# TIDA-PowerNBIoT_Buck.net
KiCad netlist of a schematic drawn in Altium Designer
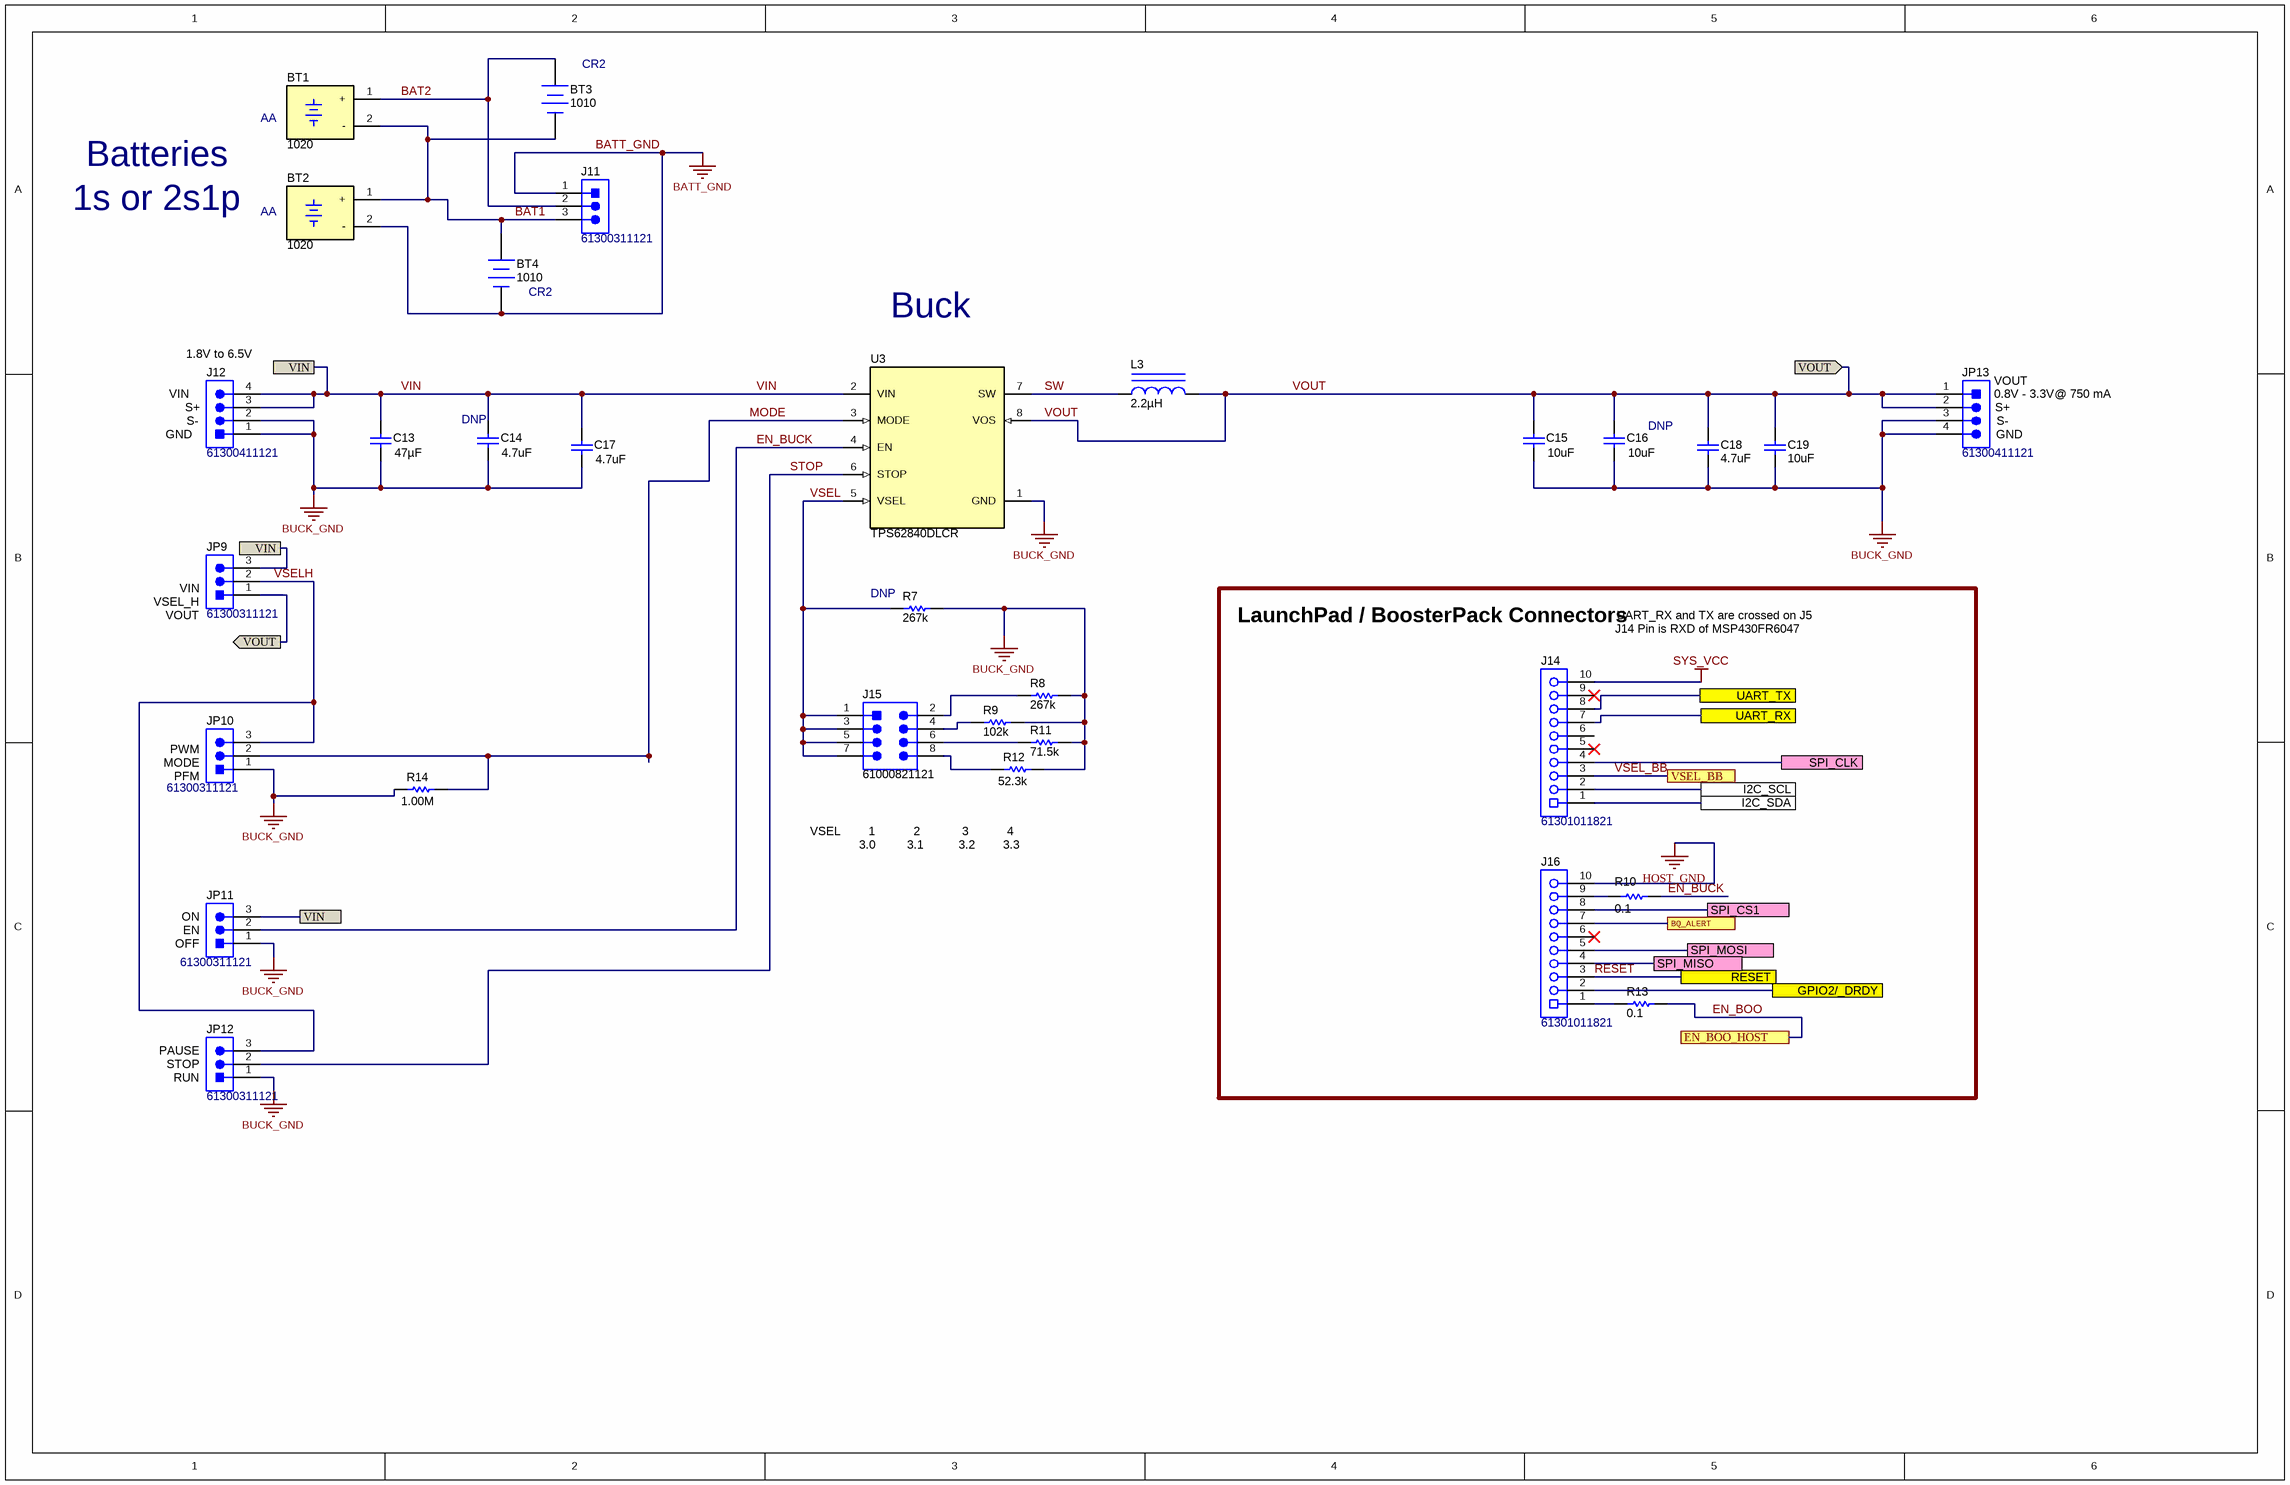
[diagram p0: TIDA-PowerNBIoT_Buck.SchDoc]

(export (version "E")
  (design (tool "Eeschema 10.0.6"))
  (components
    (comp (ref "BT1")
      (value "1020")
      (footprint "Keystone_1020")
      (description "HOLDER BATTERY AAA, SMT")
      (fields (field (name "MANUFACTURER") "Keystone") (field (name "PUBLISHER") "Texas Instruments"))
      (libsource (lib "Altium Vault - TI") (part "BatteryHolder_9V"))
    )
    (comp (ref "BT2")
      (value "1020")
      (footprint "Keystone_1020")
      (description "HOLDER BATTERY AAA, SMT")
      (fields (field (name "MANUFACTURER") "Keystone") (field (name "PUBLISHER") "Texas Instruments"))
      (libsource (lib "Altium Vault - TI") (part "BatteryHolder_9V"))
    )
    (comp (ref "BT3")
      (value "1010")
      (footprint "BAT_1010")
      (description "Battery Holder, Nylon, CR2, SMT")
      (fields (field (name "MANUFACTURER") "Keystone") (field (name "PUBLISHER") "Texas Instruments"))
      (libsource (lib "Altium Vault - TI") (part "Battery"))
    )
    (comp (ref "BT4")
      (value "1010")
      (footprint "BAT_1010")
      (description "Battery Holder, Nylon, CR2, SMT")
      (fields (field (name "MANUFACTURER") "Keystone") (field (name "PUBLISHER") "Texas Instruments"))
      (libsource (lib "Altium Vault - TI") (part "Battery"))
    )
    (comp (ref "C13")
      (value "GRM21BR61A476ME15L")
      (footprint "0805_HV")
      (description "CAP, CERM, 47 µF, 10 V,+/- 20%, X5R, 0805")
      (fields (field (name "MANUFACTURER") "MuRata") (field (name "VALUEDISPLAYED") "47µF"))
      (libsource (lib "Altium Vault - TI") (part "CMP-0078699-1"))
    )
    (comp (ref "C14")
      (value "GRM155R61A475MEAAD")
      (footprint "0402S")
      (description "CAP, CERM, 4.7 uF, 10 V, +/- 20%, X5R, 0402")
      (fields
        (field (name "MANUFACTURER") "MuRata")
        (field (name "VALUEDISPLAYED") "4.7uF")
        (field (name "PUBLISHER") "Texas Instruments")
      )
      (libsource (lib "Altium Vault - TI") (part "CMP-0006582-2"))
    )
    (comp (ref "C15")
      (value "GRM155R60G106ME44D")
      (footprint "0402_070")
      (description "CAP, CERM, 10 uF, 4 V, +/- 20%, X5R, 0402")
      (fields
        (field (name "MANUFACTURER") "MuRata")
        (field (name "VALUEDISPLAYED") "10uF")
        (field (name "PUBLISHER") "Texas Instruments")
      )
      (libsource (lib "Altium Vault - TI") (part "Capacitor"))
    )
    (comp (ref "C16")
      (value "GRM155R60G106ME44D")
      (footprint "0402_070")
      (description "CAP, CERM, 10 uF, 4 V, +/- 20%, X5R, 0402")
      (fields
        (field (name "MANUFACTURER") "MuRata")
        (field (name "VALUEDISPLAYED") "10uF")
        (field (name "PUBLISHER") "Texas Instruments")
      )
      (libsource (lib "Altium Vault - TI") (part "Capacitor"))
    )
    (comp (ref "C17")
      (value "GRM155R61A475MEAAD")
      (footprint "0402S")
      (description "CAP, CERM, 4.7 uF, 10 V, +/- 20%, X5R, 0402")
      (fields
        (field (name "MANUFACTURER") "MuRata")
        (field (name "VALUEDISPLAYED") "4.7uF")
        (field (name "PUBLISHER") "Texas Instruments")
      )
      (libsource (lib "Altium Vault - TI") (part "CMP-0006582-2"))
    )
    (comp (ref "C18")
      (value "GRM188R60J475ME19D")
      (footprint "0603S")
      (description "CAP, CERM, 4.7 uF, 6.3 V, +/- 20%, X5R, 0603")
      (fields
        (field (name "VALUEDISPLAYED") "4.7uF")
        (field (name "MANUFACTURER") "MuRata")
        (field (name "PUBLISHER") "Texas Instruments")
      )
      (libsource (lib "Altium Vault - TI") (part "CMP-0007312-5"))
    )
    (comp (ref "C19")
      (value "GRM21BR70J106KE76L")
      (footprint "0805_HV")
      (description "CAP, CERM, 10 uF, 6.3 V, +/- 10%, X7R, 0805")
      (fields
        (field (name "VALUEDISPLAYED") "10uF")
        (field (name "MANUFACTURER") "MuRata")
        (field (name "PUBLISHER") "Texas Instruments")
      )
      (libsource (lib "Altium Vault - TI") (part "Capacitor"))
    )
    (comp (ref "J11")
      (value "61300311121")
      (footprint "WURTH_61300311121")
      (description "Header, 2.54 mm, 3x1, Gold, TH")
      (fields (field (name "MANUFACTURER") "Wurth Elektronik"))
      (libsource (lib "") (part "Header_3x1_1"))
    )
    (comp (ref "J12")
      (value "61300411121")
      (footprint "WURTH_61300411121")
      (description "Header, 2.54 mm, 4x1, Gold, TH")
      (fields (field (name "MANUFACTURER") "Wurth Elektronik"))
      (libsource (lib "Altium Vault - TI") (part "Header_4x1"))
    )
    (comp (ref "J14")
      (value "61301011821")
      (footprint "Wurth_61301011821")
      (description "Receptacle, 2.54mm, 10x1, Gold, TH")
      (fields (field (name "MANUFACTURER") "Wurth Elektronik") (field (name "PUBLISHER") "Texas Instruments"))
      (libsource (lib "Altium Vault - TI") (part "Receptacle_10x1"))
    )
    (comp (ref "J15")
      (value "61000821121")
      (footprint "Wurth_61000821121")
      (description "Header, 2.54mm, 4x2, Gold, SMT")
      (fields (field (name "MANUFACTURER") "Wurth Elektronik"))
      (libsource (lib "Altium Vault - TI") (part "Header_4x2"))
    )
    (comp (ref "J16")
      (value "61301011821")
      (footprint "Wurth_61301011821")
      (description "Receptacle, 2.54mm, 10x1, Gold, TH")
      (fields (field (name "MANUFACTURER") "Wurth Elektronik") (field (name "PUBLISHER") "Texas Instruments"))
      (libsource (lib "Altium Vault - TI") (part "Receptacle_10x1"))
    )
    (comp (ref "JP9")
      (value "61300311121")
      (footprint "WURTH_61300311121")
      (description "Header, 2.54 mm, 3x1, Gold, TH")
      (fields (field (name "MANUFACTURER") "Wurth Elektronik"))
      (libsource (lib "Altium Vault - TI") (part "Header_3x1"))
    )
    (comp (ref "JP10")
      (value "61300311121")
      (footprint "WURTH_61300311121")
      (description "Header, 2.54 mm, 3x1, Gold, TH")
      (fields (field (name "MANUFACTURER") "Wurth Elektronik"))
      (libsource (lib "Altium Vault - TI") (part "Header_3x1"))
    )
    (comp (ref "JP11")
      (value "61300311121")
      (footprint "WURTH_61300311121")
      (description "Header, 2.54 mm, 3x1, Gold, TH")
      (fields (field (name "MANUFACTURER") "Wurth Elektronik"))
      (libsource (lib "Altium Vault - TI") (part "Header_3x1"))
    )
    (comp (ref "JP12")
      (value "61300311121")
      (footprint "WURTH_61300311121")
      (description "Header, 2.54 mm, 3x1, Gold, TH")
      (fields (field (name "MANUFACTURER") "Wurth Elektronik"))
      (libsource (lib "Altium Vault - TI") (part "Header_3x1"))
    )
    (comp (ref "JP13")
      (value "61300411121")
      (footprint "WURTH_61300411121")
      (description "Header, 2.54 mm, 4x1, Gold, TH")
      (fields (field (name "MANUFACTURER") "Wurth Elektronik"))
      (libsource (lib "") (part "Header_4x1_1"))
    )
    (comp (ref "L3")
      (value "DFE201612E-2R2M=P2")
      (footprint "DFE201612E")
      (description "Inductor, Shielded, Metal Composite, 2.2 µH, 1.8 A, 0.116 ohm, SMD")
      (fields (field (name "MANUFACTURER") "MuRata") (field (name "VALUEDISPLAYED") "2.2µH"))
      (libsource (lib "Altium Vault - TI") (part "Inductor_Iron"))
    )
    (comp (ref "R7")
      (value "ERJ-2RKF2673X")
      (footprint "0402")
      (description "RES, 267 k, 1%, 0.1 W, AEC-Q200 Grade 0, 0402")
      (fields
        (field (name "MANUFACTURER") "Panasonic")
        (field (name "VALUEDISPLAYED") "267k")
        (field (name "PUBLISHER") "Texas Instruments")
      )
      (libsource (lib "Altium Vault - TI") (part "Resistor"))
    )
    (comp (ref "R8")
      (value "ERJ-2RKF2673X")
      (footprint "0402")
      (description "RES, 267 k, 1%, 0.1 W, AEC-Q200 Grade 0, 0402")
      (fields
        (field (name "MANUFACTURER") "Panasonic")
        (field (name "VALUEDISPLAYED") "267k")
        (field (name "PUBLISHER") "Texas Instruments")
      )
      (libsource (lib "Altium Vault - TI") (part "Resistor"))
    )
    (comp (ref "R9")
      (value "CRCW0402102KFKED")
      (footprint "0402")
      (description "RES, 102 k, 1%, 0.063 W, 0402")
      (fields
        (field (name "MANUFACTURER") "Vishay-Dale")
        (field (name "VALUEDISPLAYED") "102k")
        (field (name "PUBLISHER") "Texas Instruments")
      )
      (libsource (lib "Altium Vault - TI") (part "Resistor"))
    )
    (comp (ref "R10")
      (value "ERJ-2BSFR10X")
      (footprint "0402")
      (description "RES, 0.1, 1%, 0.125 W, AEC-Q200 Grade 0, 0402")
      (fields (field (name "MANUFACTURER") "Panasonic") (field (name "VALUEDISPLAYED") "0.1"))
      (libsource (lib "Altium Vault - TI") (part "Resistor"))
    )
    (comp (ref "R11")
      (value "CRCW040271K5FKED")
      (footprint "0402")
      (description "RES, 71.5 k, 1%, 0.063 W, AEC-Q200 Grade 0, 0402")
      (fields (field (name "MANUFACTURER") "Vishay-Dale") (field (name "VALUEDISPLAYED") "71.5k"))
      (libsource (lib "Altium Vault - TI") (part "Resistor"))
    )
    (comp (ref "R12")
      (value "CRCW040252K3FKED")
      (footprint "0402")
      (description "RES, 52.3 k, 1%, 0.063 W, AEC-Q200 Grade 0, 0402")
      (fields (field (name "MANUFACTURER") "Vishay-Dale") (field (name "VALUEDISPLAYED") "52.3k"))
      (libsource (lib "Altium Vault - TI") (part "Resistor"))
    )
    (comp (ref "R13")
      (value "ERJ-2BSFR10X")
      (footprint "0402")
      (description "RES, 0.1, 1%, 0.125 W, AEC-Q200 Grade 0, 0402")
      (fields (field (name "MANUFACTURER") "Panasonic") (field (name "VALUEDISPLAYED") "0.1"))
      (libsource (lib "Altium Vault - TI") (part "Resistor"))
    )
    (comp (ref "R14")
      (value "CRCW04021M00FKED")
      (footprint "0402")
      (description "RES, 1.00 M, 1%, 0.063 W, AEC-Q200 Grade 0, 0402")
      (fields (field (name "MANUFACTURER") "Vishay-Dale") (field (name "VALUEDISPLAYED") "1.00M"))
      (libsource (lib "Altium Vault - TI") (part "Resistor"))
    )
    (comp (ref "U3")
      (value "TPS62840DLCR")
      (footprint "DLC0008B")
      (description "Ultra low IQ Step Down Converter, DLC0008A (VSON-HR-8)")
      (fields (field (name "MANUFACTURER") "Texas Instruments") (field (name "PARTNUMBER") "TPS62840DLCR"))
      (libsource (lib "Altium Vault - TI") (part "TPS6284xDLC"))
    )
  )
  (nets
    (net (code "1") (name "/BAT1") (class "Default")
      (node (ref "BT1") (pin "2") (pinfunction "-_2") (pintype "passive"))
      (node (ref "BT2") (pin "1") (pinfunction "+_1") (pintype "passive"))
      (node (ref "BT3") (pin "2") (pinfunction "-_2") (pintype "passive"))
      (node (ref "BT4") (pin "1") (pinfunction "+_1") (pintype "passive"))
      (node (ref "J11") (pin "3") (pinfunction "3_3") (pintype "passive"))
    )
    (net (code "2") (name "/BAT2") (class "Default")
      (node (ref "BT1") (pin "1") (pinfunction "+_1") (pintype "passive"))
      (node (ref "BT3") (pin "1") (pinfunction "+_1") (pintype "passive"))
      (node (ref "J11") (pin "2") (pinfunction "2_2") (pintype "passive"))
    )
    (net (code "3") (name "/BQ_ALERT") (class "Default")
      (node (ref "J16") (pin "7") (pinfunction "7_7") (pintype "passive"))
    )
    (net (code "4") (name "/EN_BOO") (class "Default")
      (node (ref "R13") (pin "2") (pinfunction "2_2") (pintype "passive"))
    )
    (net (code "5") (name "/EN_BUCK") (class "Default")
      (node (ref "JP11") (pin "2") (pinfunction "2_2") (pintype "passive"))
      (node (ref "R10") (pin "2") (pinfunction "2_2") (pintype "passive"))
      (node (ref "U3") (pin "4") (pinfunction "EN_4") (pintype "input"))
    )
    (net (code "6") (name "/GPIO2{slash}_DRDY") (class "Default")
      (node (ref "J16") (pin "2") (pinfunction "2_2") (pintype "passive"))
    )
    (net (code "7") (name "/I2C_SCL") (class "Default")
      (node (ref "J14") (pin "2") (pinfunction "2_2") (pintype "passive"))
    )
    (net (code "8") (name "/I2C_SDA") (class "Default")
      (node (ref "J14") (pin "1") (pinfunction "1_1") (pintype "passive"))
    )
    (net (code "9") (name "/MODE") (class "Default")
      (node (ref "JP10") (pin "2") (pinfunction "2_2") (pintype "passive"))
      (node (ref "R14") (pin "2") (pinfunction "2_2") (pintype "passive"))
      (node (ref "U3") (pin "3") (pinfunction "MODE_3") (pintype "input"))
    )
    (net (code "10") (name "/RESET") (class "Default")
      (node (ref "J16") (pin "3") (pinfunction "3_3") (pintype "passive"))
    )
    (net (code "11") (name "/SPI_CLK") (class "Default")
      (node (ref "J14") (pin "4") (pinfunction "4_4") (pintype "passive"))
    )
    (net (code "12") (name "/SPI_CS1") (class "Default")
      (node (ref "J16") (pin "8") (pinfunction "8_8") (pintype "passive"))
    )
    (net (code "13") (name "/SPI_MISO") (class "Default")
      (node (ref "J16") (pin "4") (pinfunction "4_4") (pintype "passive"))
    )
    (net (code "14") (name "/SPI_MOSI") (class "Default")
      (node (ref "J16") (pin "5") (pinfunction "5_5") (pintype "passive"))
    )
    (net (code "15") (name "/STOP") (class "Default")
      (node (ref "JP12") (pin "2") (pinfunction "2_2") (pintype "passive"))
      (node (ref "U3") (pin "6") (pinfunction "STOP_6") (pintype "input"))
    )
    (net (code "16") (name "/SW") (class "Default")
      (node (ref "L3") (pin "1") (pinfunction "1_1") (pintype "passive"))
      (node (ref "U3") (pin "7") (pinfunction "SW_7") (pintype "power_in"))
    )
    (net (code "17") (name "/UART_RX") (class "Default")
      (node (ref "J14") (pin "7") (pinfunction "7_7") (pintype "passive"))
    )
    (net (code "18") (name "/UART_TX") (class "Default")
      (node (ref "J14") (pin "8") (pinfunction "8_8") (pintype "passive"))
    )
    (net (code "19") (name "/VIN") (class "Default")
      (node (ref "C13") (pin "1") (pinfunction "1_1") (pintype "passive"))
      (node (ref "C14") (pin "1") (pinfunction "1_1") (pintype "passive"))
      (node (ref "C17") (pin "1") (pinfunction "1_1") (pintype "passive"))
      (node (ref "J12") (pin "3") (pinfunction "3_3") (pintype "passive"))
      (node (ref "J12") (pin "4") (pinfunction "4_4") (pintype "passive"))
      (node (ref "JP11") (pin "3") (pinfunction "3_3") (pintype "passive"))
      (node (ref "JP9") (pin "3") (pinfunction "3_3") (pintype "passive"))
      (node (ref "U3") (pin "2") (pinfunction "VIN_2") (pintype "power_in"))
    )
    (net (code "20") (name "/VOUT") (class "Default")
      (node (ref "C15") (pin "1") (pinfunction "1_1") (pintype "passive"))
      (node (ref "C16") (pin "1") (pinfunction "1_1") (pintype "passive"))
      (node (ref "C18") (pin "1") (pinfunction "1_1") (pintype "passive"))
      (node (ref "C19") (pin "1") (pinfunction "1_1") (pintype "passive"))
      (node (ref "JP13") (pin "1") (pinfunction "1_1") (pintype "passive"))
      (node (ref "JP13") (pin "2") (pinfunction "2_2") (pintype "passive"))
      (node (ref "JP9") (pin "1") (pinfunction "1_1") (pintype "passive"))
      (node (ref "L3") (pin "2") (pinfunction "2_2") (pintype "passive"))
      (node (ref "U3") (pin "8") (pinfunction "VOS_8") (pintype "input"))
    )
    (net (code "21") (name "/VSEL") (class "Default")
      (node (ref "J15") (pin "1") (pinfunction "1_1") (pintype "passive"))
      (node (ref "J15") (pin "3") (pinfunction "3_3") (pintype "passive"))
      (node (ref "J15") (pin "5") (pinfunction "5_5") (pintype "passive"))
      (node (ref "J15") (pin "7") (pinfunction "7_7") (pintype "passive"))
      (node (ref "R7") (pin "1") (pinfunction "1_1") (pintype "passive"))
      (node (ref "U3") (pin "5") (pinfunction "VSEL_5") (pintype "input"))
    )
    (net (code "22") (name "/VSELH") (class "Default")
      (node (ref "JP10") (pin "3") (pinfunction "3_3") (pintype "passive"))
      (node (ref "JP12") (pin "3") (pinfunction "3_3") (pintype "passive"))
      (node (ref "JP9") (pin "2") (pinfunction "2_2") (pintype "passive"))
    )
    (net (code "23") (name "/VSEL_BB") (class "Default")
      (node (ref "J14") (pin "3") (pinfunction "3_3") (pintype "passive"))
    )
    (net (code "24") (name "BATT_GND") (class "Default")
      (node (ref "BT2") (pin "2") (pinfunction "-_2") (pintype "passive"))
      (node (ref "BT4") (pin "2") (pinfunction "-_2") (pintype "passive"))
      (node (ref "J11") (pin "1") (pinfunction "1_1") (pintype "passive"))
    )
    (net (code "25") (name "BUCK_GND") (class "Default")
      (node (ref "C13") (pin "2") (pinfunction "2_2") (pintype "passive"))
      (node (ref "C14") (pin "2") (pinfunction "2_2") (pintype "passive"))
      (node (ref "C15") (pin "2") (pinfunction "2_2") (pintype "passive"))
      (node (ref "C16") (pin "2") (pinfunction "2_2") (pintype "passive"))
      (node (ref "C17") (pin "2") (pinfunction "2_2") (pintype "passive"))
      (node (ref "C18") (pin "2") (pinfunction "2_2") (pintype "passive"))
      (node (ref "C19") (pin "2") (pinfunction "2_2") (pintype "passive"))
      (node (ref "J12") (pin "1") (pinfunction "1_1") (pintype "passive"))
      (node (ref "J12") (pin "2") (pinfunction "2_2") (pintype "passive"))
      (node (ref "JP10") (pin "1") (pinfunction "1_1") (pintype "passive"))
      (node (ref "JP11") (pin "1") (pinfunction "1_1") (pintype "passive"))
      (node (ref "JP12") (pin "1") (pinfunction "1_1") (pintype "passive"))
      (node (ref "JP13") (pin "3") (pinfunction "3_3") (pintype "passive"))
      (node (ref "JP13") (pin "4") (pinfunction "4_4") (pintype "passive"))
      (node (ref "R11") (pin "2") (pinfunction "2_2") (pintype "passive"))
      (node (ref "R12") (pin "2") (pinfunction "2_2") (pintype "passive"))
      (node (ref "R14") (pin "1") (pinfunction "1_1") (pintype "passive"))
      (node (ref "R7") (pin "2") (pinfunction "2_2") (pintype "passive"))
      (node (ref "R8") (pin "2") (pinfunction "2_2") (pintype "passive"))
      (node (ref "R9") (pin "2") (pinfunction "2_2") (pintype "passive"))
      (node (ref "U3") (pin "1") (pinfunction "GND_1") (pintype "power_in"))
    )
    (net (code "26") (name "HOST_GND") (class "Default")
      (node (ref "J16") (pin "10") (pinfunction "10_10") (pintype "passive"))
    )
    (net (code "27") (name "Net-(J15-Pad2)") (class "Default")
      (node (ref "J15") (pin "2") (pinfunction "2_2") (pintype "passive"))
      (node (ref "R8") (pin "1") (pinfunction "1_1") (pintype "passive"))
    )
    (net (code "28") (name "Net-(J15-Pad4)") (class "Default")
      (node (ref "J15") (pin "4") (pinfunction "4_4") (pintype "passive"))
      (node (ref "R9") (pin "1") (pinfunction "1_1") (pintype "passive"))
    )
    (net (code "29") (name "Net-(J15-Pad6)") (class "Default")
      (node (ref "J15") (pin "6") (pinfunction "6_6") (pintype "passive"))
      (node (ref "R11") (pin "1") (pinfunction "1_1") (pintype "passive"))
    )
    (net (code "30") (name "Net-(J15-Pad8)") (class "Default")
      (node (ref "J15") (pin "8") (pinfunction "8_8") (pintype "passive"))
      (node (ref "R12") (pin "1") (pinfunction "1_1") (pintype "passive"))
    )
    (net (code "31") (name "Net-(J16-Pad1)") (class "Default")
      (node (ref "J16") (pin "1") (pinfunction "1_1") (pintype "passive"))
      (node (ref "R13") (pin "1") (pinfunction "1_1") (pintype "passive"))
    )
    (net (code "32") (name "Net-(J16-Pad9)") (class "Default")
      (node (ref "J16") (pin "9") (pinfunction "9_9") (pintype "passive"))
      (node (ref "R10") (pin "1") (pinfunction "1_1") (pintype "passive"))
    )
    (net (code "33") (name "SYS_VCC") (class "Default")
      (node (ref "J14") (pin "10") (pinfunction "10_10") (pintype "passive"))
    )
    (net (code "34") (name "unconnected-(J14-Pad5)") (class "Default")
      (node (ref "J14") (pin "5") (pinfunction "5_5") (pintype "passive+no_connect"))
    )
    (net (code "35") (name "unconnected-(J14-Pad6)") (class "Default")
      (node (ref "J14") (pin "6") (pinfunction "6_6") (pintype "passive"))
    )
    (net (code "36") (name "unconnected-(J14-Pad9)") (class "Default")
      (node (ref "J14") (pin "9") (pinfunction "9_9") (pintype "passive+no_connect"))
    )
    (net (code "37") (name "unconnected-(J16-Pad6)") (class "Default")
      (node (ref "J16") (pin "6") (pinfunction "6_6") (pintype "passive+no_connect"))
    )
  )
)
